# MurataMicroMB.net
KiCad netlist of a schematic drawn in EAGLE
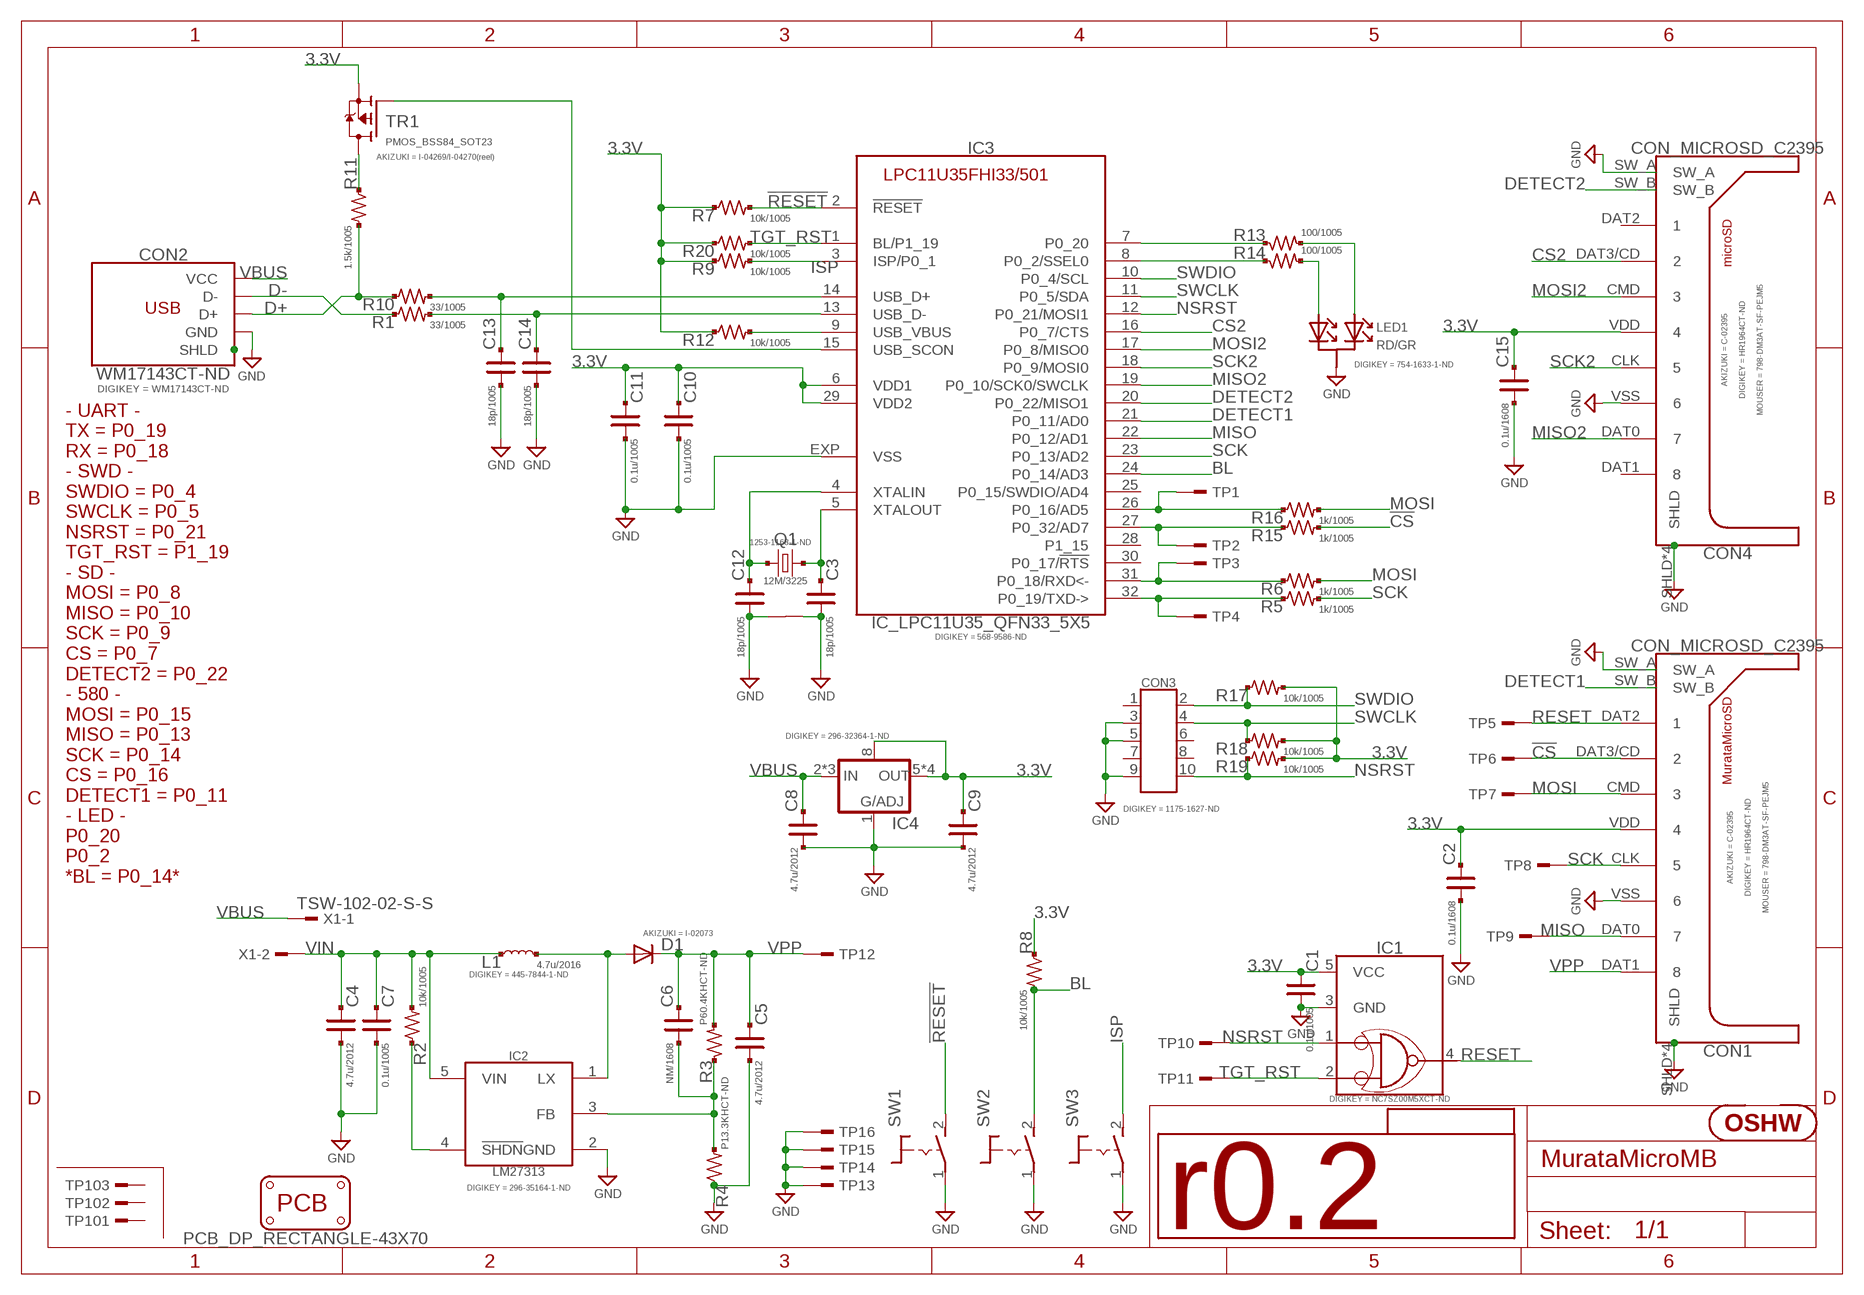
[diagram p0: schematic, sheet 1]

(export (version "E")
  (design (tool "Eeschema 10.0.6"))
  (components
    (comp (ref "C1")
      (value "0.1u/1005")
      (footprint "eagle-import:C0402")
      (libsource (lib "eagle-import") (part "C_SMD__10050.1U"))
    )
    (comp (ref "C2")
      (value "0.1u/1608")
      (footprint "eagle-import:CR_1608")
      (libsource (lib "eagle-import") (part "C_SMD__16080.1U"))
    )
    (comp (ref "C3")
      (value "18p/1005")
      (footprint "eagle-import:C0402")
      (libsource (lib "eagle-import") (part "C_SMD__100518P"))
    )
    (comp (ref "C4")
      (value "4.7u/2012")
      (footprint "eagle-import:CR_2125")
      (libsource (lib "eagle-import") (part "C_SMD__20124.7U"))
    )
    (comp (ref "C5")
      (value "4.7u/2012")
      (footprint "eagle-import:CR_2125")
      (libsource (lib "eagle-import") (part "C_SMD__20124.7U"))
    )
    (comp (ref "C6")
      (value "NM/1608")
      (footprint "eagle-import:CR_1608")
      (libsource (lib "eagle-import") (part "C_SMD__1608"))
    )
    (comp (ref "C7")
      (value "0.1u/1005")
      (footprint "eagle-import:C0402")
      (libsource (lib "eagle-import") (part "C_SMD__10050.1U"))
    )
    (comp (ref "C8")
      (value "4.7u/2012")
      (footprint "eagle-import:CR_2125")
      (libsource (lib "eagle-import") (part "C_SMD__20124.7U"))
    )
    (comp (ref "C9")
      (value "4.7u/2012")
      (footprint "eagle-import:CR_2125")
      (libsource (lib "eagle-import") (part "C_SMD__20124.7U"))
    )
    (comp (ref "C10")
      (value "0.1u/1005")
      (footprint "eagle-import:C0402")
      (libsource (lib "eagle-import") (part "C_SMD__10050.1U"))
    )
    (comp (ref "C11")
      (value "0.1u/1005")
      (footprint "eagle-import:C0402")
      (libsource (lib "eagle-import") (part "C_SMD__10050.1U"))
    )
    (comp (ref "C12")
      (value "18p/1005")
      (footprint "eagle-import:C0402")
      (libsource (lib "eagle-import") (part "C_SMD__100518P"))
    )
    (comp (ref "C13")
      (value "18p/1005")
      (footprint "eagle-import:C0402")
      (libsource (lib "eagle-import") (part "C_SMD__100518P"))
    )
    (comp (ref "C14")
      (value "18p/1005")
      (footprint "eagle-import:C0402")
      (libsource (lib "eagle-import") (part "C_SMD__100518P"))
    )
    (comp (ref "C15")
      (value "0.1u/1608")
      (footprint "eagle-import:CR_1608")
      (libsource (lib "eagle-import") (part "C_SMD__16080.1U"))
    )
    (comp (ref "CON1")
      (value "CON_MICROSD_C2395")
      (footprint "eagle-import:CON_MICROSD_C2395")
      (fields
        (field (name "AKIZUKI") "C-02395")
        (field (name "DIGIKEY") "HR1964CT-ND")
        (field (name "MOUSER") "798-DM3AT-SF-PEJM5")
      )
      (libsource (lib "eagle-import") (part "CON_MICROSD_C2395"))
    )
    (comp (ref "CON2")
      (value "WM17143CT-ND")
      (footprint "eagle-import:CON_USB_47589-0001MOLEX")
      (fields (field (name "DIGIKEY") "WM17143CT-ND"))
      (libsource (lib "eagle-import") (part "CON_USB_UB"))
    )
    (comp (ref "CON3")
      (value "CON_MIL_10_ARM")
      (footprint "eagle-import:CON_CORESIGHT10_1175-1627-ND")
      (fields (field (name "DIGIKEY") "1175-1627-ND"))
      (libsource (lib "eagle-import") (part "CON_MIL_10_ARM"))
    )
    (comp (ref "CON4")
      (value "CON_MICROSD_C2395")
      (footprint "eagle-import:CON_MICROSD_C2395")
      (fields
        (field (name "AKIZUKI") "C-02395")
        (field (name "DIGIKEY") "HR1964CT-ND")
        (field (name "MOUSER") "798-DM3AT-SF-PEJM5")
      )
      (libsource (lib "eagle-import") (part "CON_MICROSD_C2395"))
    )
    (comp (ref "D1")
      (value "40V2A")
      (footprint "eagle-import:DIODE_2125")
      (fields (field (name "AKIZUKI") "I-02073"))
      (libsource (lib "eagle-import") (part "DIODE2__SOD12340V2A"))
    )
    (comp (ref "GIT1")
      (value "GIT-REVISION")
      (footprint "eagle-import:GIT-REVISION")
      (libsource (lib "eagle-import") (part "GIT-REVISION"))
    )
    (comp (ref "IC1")
      (value "IC_TTL_SINGLE_74_00_SOT23")
      (footprint "eagle-import:SOT95P280X145-5N")
      (fields (field (name "DIGIKEY") "NC7SZ00M5XCT-ND"))
      (libsource (lib "eagle-import") (part "IC_TTL_SINGLE_74_00_SOT23"))
    )
    (comp (ref "IC2")
      (value "LM27313")
      (footprint "eagle-import:SOT95P280X145-5N")
      (fields (field (name "DIGIKEY") "296-35164-1-ND"))
      (libsource (lib "eagle-import") (part "IC_DCDC_LM27313_SOT23"))
    )
    (comp (ref "IC3")
      (value "IC_LPC11U35_QFN33_5X5")
      (footprint "eagle-import:HVQFN33")
      (fields (field (name "DIGIKEY") "568-9586-ND"))
      (libsource (lib "eagle-import") (part "IC_LPC11U_QFN33_5X535"))
    )
    (comp (ref "IC4")
      (value "LDO4_3.3_DRJ")
      (footprint "eagle-import:DFN80P410X410_8N")
      (fields (field (name "DIGIKEY") "296-32364-1-ND"))
      (libsource (lib "eagle-import") (part "LDO4__DRJ3.3"))
    )
    (comp (ref "ICON1")
      (value "r0.2")
      (footprint "eagle-import:ICON_REVISION2.0")
      (libsource (lib "eagle-import") (part "ICON_REVISION_2.0"))
    )
    (comp (ref "L1")
      (value "4.7u/2016")
      (footprint "eagle-import:L_2016")
      (fields (field (name "DIGIKEY") "445-7844-1-ND"))
      (libsource (lib "eagle-import") (part "INDUCTOR__20164.7U"))
    )
    (comp (ref "LED1")
      (value "RD/GR")
      (footprint "eagle-import:SOT105P300X130-3N")
      (fields (field (name "DIGIKEY") "754-1633-1-ND "))
      (libsource (lib "eagle-import") (part "LED2_A2K1_GR/RD"))
    )
    (comp (ref "PCB1")
      (value "PCB_DP_RECTANGLE-43X70")
      (footprint "eagle-import:DP7043_V1")
      (libsource (lib "eagle-import") (part "PCB_DP_RECTANGLE-43X70"))
    )
    (comp (ref "Q1")
      (value "12M/3225")
      (footprint "eagle-import:CLOCK_3225")
      (fields (field (name "DIGIKEY") "1253-1168-1-ND"))
      (libsource (lib "eagle-import") (part "CRYSTAL4__322512M"))
    )
    (comp (ref "R1")
      (value "33/1005")
      (footprint "eagle-import:C0402")
      (libsource (lib "eagle-import") (part "R_US__100533R"))
    )
    (comp (ref "R2")
      (value "10k/1005")
      (footprint "eagle-import:C0402")
      (libsource (lib "eagle-import") (part "R_US__100510K"))
    )
    (comp (ref "R3")
      (value "P60.4KHCT-ND")
      (footprint "eagle-import:R_1608_PADPAD")
      (libsource (lib "eagle-import") (part "R_US__160860.4K"))
    )
    (comp (ref "R4")
      (value "P13.3KHCT-ND")
      (footprint "eagle-import:R_1608_PADPAD")
      (libsource (lib "eagle-import") (part "R_US__160813.3K"))
    )
    (comp (ref "R5")
      (value "1k/1005")
      (footprint "eagle-import:C0402")
      (libsource (lib "eagle-import") (part "R_US__10051.0K"))
    )
    (comp (ref "R6")
      (value "1k/1005")
      (footprint "eagle-import:C0402")
      (libsource (lib "eagle-import") (part "R_US__10051.0K"))
    )
    (comp (ref "R7")
      (value "10k/1005")
      (footprint "eagle-import:C0402")
      (libsource (lib "eagle-import") (part "R_US__100510K"))
    )
    (comp (ref "R8")
      (value "10k/1005")
      (footprint "eagle-import:C0402")
      (libsource (lib "eagle-import") (part "R_US__100510K"))
    )
    (comp (ref "R9")
      (value "10k/1005")
      (footprint "eagle-import:C0402")
      (libsource (lib "eagle-import") (part "R_US__100510K"))
    )
    (comp (ref "R10")
      (value "33/1005")
      (footprint "eagle-import:C0402")
      (libsource (lib "eagle-import") (part "R_US__100533R"))
    )
    (comp (ref "R11")
      (value "1.5k/1005")
      (footprint "eagle-import:C0402")
      (libsource (lib "eagle-import") (part "R_US__10051.5K"))
    )
    (comp (ref "R12")
      (value "10k/1005")
      (footprint "eagle-import:C0402")
      (libsource (lib "eagle-import") (part "R_US__100510K"))
    )
    (comp (ref "R13")
      (value "100/1005")
      (footprint "eagle-import:C0402")
      (libsource (lib "eagle-import") (part "R_US__1005100R"))
    )
    (comp (ref "R14")
      (value "100/1005")
      (footprint "eagle-import:C0402")
      (libsource (lib "eagle-import") (part "R_US__1005100R"))
    )
    (comp (ref "R15")
      (value "1k/1005")
      (footprint "eagle-import:C0402")
      (libsource (lib "eagle-import") (part "R_US__10051.0K"))
    )
    (comp (ref "R16")
      (value "1k/1005")
      (footprint "eagle-import:C0402")
      (libsource (lib "eagle-import") (part "R_US__10051.0K"))
    )
    (comp (ref "R17")
      (value "10k/1005")
      (footprint "eagle-import:C0402")
      (libsource (lib "eagle-import") (part "R_US__100510K"))
    )
    (comp (ref "R18")
      (value "10k/1005")
      (footprint "eagle-import:C0402")
      (libsource (lib "eagle-import") (part "R_US__100510K"))
    )
    (comp (ref "R19")
      (value "10k/1005")
      (footprint "eagle-import:C0402")
      (libsource (lib "eagle-import") (part "R_US__100510K"))
    )
    (comp (ref "R20")
      (value "10k/1005")
      (footprint "eagle-import:C0402")
      (libsource (lib "eagle-import") (part "R_US__100510K"))
    )
    (comp (ref "SW1")
      (value "TACTSW2_FSM2JMTR")
      (footprint "eagle-import:SW_TACTSW_FSM2JMTR")
      (libsource (lib "eagle-import") (part "TACTSW2_FSM2JMTR"))
    )
    (comp (ref "SW2")
      (value "TACTSW2_FSM2JMTR")
      (footprint "eagle-import:SW_TACTSW_FSM2JMTR")
      (libsource (lib "eagle-import") (part "TACTSW2_FSM2JMTR"))
    )
    (comp (ref "SW3")
      (value "TACTSW2_FSM2JMTR")
      (footprint "eagle-import:SW_TACTSW_FSM2JMTR")
      (libsource (lib "eagle-import") (part "TACTSW2_FSM2JMTR"))
    )
    (comp (ref "TP1")
      (value "TESTPAD_1608")
      (footprint "eagle-import:TP_1608")
      (libsource (lib "eagle-import") (part "TESTPAD_1608"))
    )
    (comp (ref "TP2")
      (value "TESTPAD_1608")
      (footprint "eagle-import:TP_1608")
      (libsource (lib "eagle-import") (part "TESTPAD_1608"))
    )
    (comp (ref "TP3")
      (value "TESTPAD_1608")
      (footprint "eagle-import:TP_1608")
      (libsource (lib "eagle-import") (part "TESTPAD_1608"))
    )
    (comp (ref "TP4")
      (value "TESTPAD_1608")
      (footprint "eagle-import:TP_1608")
      (libsource (lib "eagle-import") (part "TESTPAD_1608"))
    )
    (comp (ref "TP5")
      (value "TESTPAD")
      (footprint "eagle-import:TP06RECT")
      (libsource (lib "eagle-import") (part "TESTPAD"))
    )
    (comp (ref "TP6")
      (value "TESTPAD")
      (footprint "eagle-import:TP06RECT")
      (libsource (lib "eagle-import") (part "TESTPAD"))
    )
    (comp (ref "TP7")
      (value "TESTPAD")
      (footprint "eagle-import:TP06RECT")
      (libsource (lib "eagle-import") (part "TESTPAD"))
    )
    (comp (ref "TP8")
      (value "TESTPAD")
      (footprint "eagle-import:TP06RECT")
      (libsource (lib "eagle-import") (part "TESTPAD"))
    )
    (comp (ref "TP9")
      (value "TESTPAD")
      (footprint "eagle-import:TP06RECT")
      (libsource (lib "eagle-import") (part "TESTPAD"))
    )
    (comp (ref "TP10")
      (value "TESTPAD")
      (footprint "eagle-import:TP06RECT")
      (libsource (lib "eagle-import") (part "TESTPAD"))
    )
    (comp (ref "TP11")
      (value "TESTPAD")
      (footprint "eagle-import:TP06RECT")
      (libsource (lib "eagle-import") (part "TESTPAD"))
    )
    (comp (ref "TP12")
      (value "TESTPAD")
      (footprint "eagle-import:TP06RECT")
      (libsource (lib "eagle-import") (part "TESTPAD"))
    )
    (comp (ref "TP13")
      (value "TESTPAD_4020")
      (footprint "eagle-import:TP_4020")
      (libsource (lib "eagle-import") (part "TESTPAD_4020"))
    )
    (comp (ref "TP14")
      (value "TESTPAD_4020")
      (footprint "eagle-import:TP_4020")
      (libsource (lib "eagle-import") (part "TESTPAD_4020"))
    )
    (comp (ref "TP15")
      (value "TESTPAD_4020")
      (footprint "eagle-import:TP_4020")
      (libsource (lib "eagle-import") (part "TESTPAD_4020"))
    )
    (comp (ref "TP16")
      (value "TESTPAD_4020")
      (footprint "eagle-import:TP_4020")
      (libsource (lib "eagle-import") (part "TESTPAD_4020"))
    )
    (comp (ref "TP101")
      (value "TESTPAD_F")
      (footprint "eagle-import:FIDUCIAL")
      (libsource (lib "eagle-import") (part "TESTPAD_F"))
    )
    (comp (ref "TP102")
      (value "TESTPAD_F")
      (footprint "eagle-import:FIDUCIAL")
      (libsource (lib "eagle-import") (part "TESTPAD_F"))
    )
    (comp (ref "TP103")
      (value "TESTPAD_F")
      (footprint "eagle-import:FIDUCIAL")
      (libsource (lib "eagle-import") (part "TESTPAD_F"))
    )
    (comp (ref "TR1")
      (value "PMOS_BSS84_SOT23")
      (footprint "eagle-import:SOT95P300X140-3N")
      (fields (field (name "AKIZUKI") "I-04269/I-04270(reel)"))
      (libsource (lib "eagle-import") (part "PMOS__SOT23BSS84"))
    )
    (comp (ref "U$1")
      (value "ICON_OSHW")
      (footprint "eagle-import:ICON_OSHW")
      (libsource (lib "eagle-import") (part "ICON_OSHW"))
    )
    (comp (ref "X1")
      (value "TSW-102-02-S-S")
      (footprint "eagle-import:TSW-102-02-S-S")
      (libsource (lib "eagle-import") (part "TSW-102-02-S-S"))
    )
  )
  (nets
    (net (code "1") (name "/3.3V") (class "Default")
      (node (ref "C1") (pin "1") (pinfunction "1_1") (pintype "passive"))
      (node (ref "C10") (pin "1") (pinfunction "1_1") (pintype "passive"))
      (node (ref "C11") (pin "1") (pinfunction "1_1") (pintype "passive"))
      (node (ref "C15") (pin "1") (pinfunction "1_1") (pintype "passive"))
      (node (ref "C2") (pin "1") (pinfunction "1_1") (pintype "passive"))
      (node (ref "C9") (pin "1") (pinfunction "1_1") (pintype "passive"))
      (node (ref "CON1") (pin "VDD") (pinfunction "4_VDD") (pintype "power_in"))
      (node (ref "CON4") (pin "VDD") (pinfunction "4_VDD") (pintype "power_in"))
      (node (ref "IC1") (pin "5") (pinfunction "VCC_5") (pintype "power_in"))
      (node (ref "IC3") (pin "29") (pinfunction "VDD2_29") (pintype "bidirectional"))
      (node (ref "IC3") (pin "6") (pinfunction "VDD1_6") (pintype "bidirectional"))
      (node (ref "IC4") (pin "5") (pinfunction "OUT_5") (pintype "power_in"))
      (node (ref "IC4") (pin "6") (pinfunction "OUT_6") (pintype "power_in"))
      (node (ref "IC4") (pin "7") (pinfunction "OUT_7") (pintype "power_in"))
      (node (ref "IC4") (pin "8") (pinfunction "OUT/EN/NC_8") (pintype "tri_state"))
      (node (ref "IC4") (pin "EP") (pinfunction "OUT_EP") (pintype "power_in"))
      (node (ref "R12") (pin "1") (pinfunction "1_1") (pintype "passive"))
      (node (ref "R17") (pin "2") (pinfunction "2_2") (pintype "passive"))
      (node (ref "R18") (pin "2") (pinfunction "2_2") (pintype "passive"))
      (node (ref "R19") (pin "2") (pinfunction "2_2") (pintype "passive"))
      (node (ref "R20") (pin "1") (pinfunction "1_1") (pintype "passive"))
      (node (ref "R7") (pin "1") (pinfunction "1_1") (pintype "passive"))
      (node (ref "R8") (pin "1") (pinfunction "1_1") (pintype "passive"))
      (node (ref "R9") (pin "1") (pinfunction "1_1") (pintype "passive"))
      (node (ref "TR1") (pin "2") (pinfunction "S_2") (pintype "passive"))
    )
    (net (code "2") (name "/BL") (class "Default")
      (node (ref "IC3") (pin "24") (pinfunction "P0_14/AD3_24") (pintype "bidirectional"))
      (node (ref "R8") (pin "2") (pinfunction "2_2") (pintype "passive"))
      (node (ref "SW2") (pin "2") (pinfunction "S_2") (pintype "passive"))
    )
    (net (code "3") (name "/CS2") (class "Default")
      (node (ref "CON4") (pin "DAT3/CD") (pinfunction "2_DAT3/CD") (pintype "bidirectional"))
      (node (ref "IC3") (pin "16") (pinfunction "P0_7/CTS_16") (pintype "bidirectional"))
    )
    (net (code "4") (name "/D+") (class "Default")
      (node (ref "CON2") (pin "3") (pinfunction "D+_3") (pintype "bidirectional"))
      (node (ref "R10") (pin "1") (pinfunction "1_1") (pintype "passive"))
      (node (ref "R11") (pin "2") (pinfunction "2_2") (pintype "passive"))
    )
    (net (code "5") (name "/D-") (class "Default")
      (node (ref "CON2") (pin "2") (pinfunction "D-_2") (pintype "bidirectional"))
      (node (ref "R1") (pin "1") (pinfunction "1_1") (pintype "passive"))
    )
    (net (code "6") (name "/DETECT1") (class "Default")
      (node (ref "CON1") (pin "SW_B") (pinfunction "SW_B_SW_B") (pintype "bidirectional"))
      (node (ref "IC3") (pin "21") (pinfunction "P0_11/AD0_21") (pintype "bidirectional"))
    )
    (net (code "7") (name "/DETECT2") (class "Default")
      (node (ref "CON4") (pin "SW_B") (pinfunction "SW_B_SW_B") (pintype "bidirectional"))
      (node (ref "IC3") (pin "20") (pinfunction "P0_22/MISO1_20") (pintype "bidirectional"))
    )
    (net (code "8") (name "/ISP") (class "Default")
      (node (ref "IC3") (pin "3") (pinfunction "ISP/P0_1_3") (pintype "bidirectional"))
      (node (ref "R9") (pin "2") (pinfunction "2_2") (pintype "passive"))
      (node (ref "SW3") (pin "2") (pinfunction "S_2") (pintype "passive"))
    )
    (net (code "9") (name "/MISO") (class "Default")
      (node (ref "CON1") (pin "DAT0") (pinfunction "7_DAT0") (pintype "bidirectional"))
      (node (ref "IC3") (pin "22") (pinfunction "P0_12/AD1_22") (pintype "bidirectional"))
      (node (ref "TP9") (pin "TP") (pinfunction "1_TP") (pintype "passive"))
    )
    (net (code "10") (name "/MISO2") (class "Default")
      (node (ref "CON4") (pin "DAT0") (pinfunction "7_DAT0") (pintype "bidirectional"))
      (node (ref "IC3") (pin "19") (pinfunction "P0_10/SCK0/SWCLK_19") (pintype "bidirectional"))
    )
    (net (code "11") (name "/MOSI") (class "Default")
      (node (ref "CON1") (pin "CMD") (pinfunction "3_CMD") (pintype "bidirectional"))
      (node (ref "R16") (pin "2") (pinfunction "2_2") (pintype "passive"))
      (node (ref "R6") (pin "2") (pinfunction "2_2") (pintype "passive"))
      (node (ref "TP7") (pin "TP") (pinfunction "1_TP") (pintype "passive"))
    )
    (net (code "12") (name "/MOSI2") (class "Default")
      (node (ref "CON4") (pin "CMD") (pinfunction "3_CMD") (pintype "bidirectional"))
      (node (ref "IC3") (pin "17") (pinfunction "P0_8/MISO0_17") (pintype "bidirectional"))
    )
    (net (code "13") (name "/NSRST") (class "Default")
      (node (ref "CON3") (pin "10") (pinfunction "10_10") (pintype "bidirectional"))
      (node (ref "IC1") (pin "1") (pinfunction "1A_1") (pintype "input"))
      (node (ref "IC3") (pin "12") (pinfunction "P0_21/MOSI1_12") (pintype "bidirectional"))
      (node (ref "R19") (pin "1") (pinfunction "1_1") (pintype "passive"))
      (node (ref "TP10") (pin "TP") (pinfunction "1_TP") (pintype "passive"))
    )
    (net (code "14") (name "/RESET") (class "Default")
      (node (ref "CON1") (pin "DAT2") (pinfunction "1_DAT2") (pintype "bidirectional"))
      (node (ref "IC1") (pin "4") (pinfunction "1Y_4") (pintype "output"))
      (node (ref "TP5") (pin "TP") (pinfunction "1_TP") (pintype "passive"))
    )
    (net (code "15") (name "/SCK") (class "Default")
      (node (ref "CON1") (pin "CLK") (pinfunction "5_CLK") (pintype "bidirectional"))
      (node (ref "IC3") (pin "23") (pinfunction "P0_13/AD2_23") (pintype "bidirectional"))
      (node (ref "R5") (pin "2") (pinfunction "2_2") (pintype "passive"))
      (node (ref "TP8") (pin "TP") (pinfunction "1_TP") (pintype "passive"))
    )
    (net (code "16") (name "/SCK2") (class "Default")
      (node (ref "CON4") (pin "CLK") (pinfunction "5_CLK") (pintype "bidirectional"))
      (node (ref "IC3") (pin "18") (pinfunction "P0_9/MOSI0_18") (pintype "bidirectional"))
    )
    (net (code "17") (name "/SWCLK") (class "Default")
      (node (ref "CON3") (pin "4") (pinfunction "4_4") (pintype "bidirectional"))
      (node (ref "IC3") (pin "11") (pinfunction "P0_5/SDA_11") (pintype "bidirectional"))
      (node (ref "R18") (pin "1") (pinfunction "1_1") (pintype "passive"))
    )
    (net (code "18") (name "/SWDIO") (class "Default")
      (node (ref "CON3") (pin "2") (pinfunction "2_2") (pintype "bidirectional"))
      (node (ref "IC3") (pin "10") (pinfunction "P0_4/SCL_10") (pintype "bidirectional"))
      (node (ref "R17") (pin "1") (pinfunction "1_1") (pintype "passive"))
    )
    (net (code "19") (name "/TGT_RST") (class "Default")
      (node (ref "IC1") (pin "2") (pinfunction "1B_2") (pintype "input"))
      (node (ref "IC3") (pin "1") (pinfunction "BL/P1_19_1") (pintype "bidirectional"))
      (node (ref "R20") (pin "2") (pinfunction "2_2") (pintype "passive"))
      (node (ref "TP11") (pin "TP") (pinfunction "1_TP") (pintype "passive"))
    )
    (net (code "20") (name "/VBUS") (class "Default")
      (node (ref "C8") (pin "1") (pinfunction "1_1") (pintype "passive"))
      (node (ref "CON2") (pin "1") (pinfunction "VCC_1") (pintype "power_in"))
      (node (ref "IC4") (pin "2") (pinfunction "IN_2") (pintype "power_in"))
      (node (ref "IC4") (pin "3") (pinfunction "IN_3") (pintype "power_in"))
      (node (ref "IC4") (pin "4") (pinfunction "IN_4") (pintype "power_in"))
      (node (ref "X1") (pin "1") (pinfunction "1_1") (pintype "passive"))
    )
    (net (code "21") (name "/VIN") (class "Default")
      (node (ref "C4") (pin "1") (pinfunction "1_1") (pintype "passive"))
      (node (ref "C7") (pin "1") (pinfunction "1_1") (pintype "passive"))
      (node (ref "IC2") (pin "5") (pinfunction "VIN_5") (pintype "bidirectional"))
      (node (ref "L1") (pin "1") (pinfunction "1_1") (pintype "passive"))
      (node (ref "R2") (pin "2") (pinfunction "2_2") (pintype "passive"))
      (node (ref "X1") (pin "2") (pinfunction "1_2") (pintype "passive"))
    )
    (net (code "22") (name "/VPP") (class "Default")
      (node (ref "C5") (pin "1") (pinfunction "1_1") (pintype "passive"))
      (node (ref "C6") (pin "1") (pinfunction "1_1") (pintype "passive"))
      (node (ref "CON1") (pin "DAT1") (pinfunction "8_DAT1") (pintype "bidirectional"))
      (node (ref "D1") (pin "K") (pinfunction "C_K") (pintype "passive"))
      (node (ref "R3") (pin "2") (pinfunction "2_2") (pintype "passive"))
      (node (ref "TP12") (pin "TP") (pinfunction "1_TP") (pintype "passive"))
    )
    (net (code "23") (name "/~{CS}") (class "Default")
      (node (ref "CON1") (pin "DAT3/CD") (pinfunction "2_DAT3/CD") (pintype "bidirectional"))
      (node (ref "R15") (pin "2") (pinfunction "2_2") (pintype "passive"))
      (node (ref "TP6") (pin "TP") (pinfunction "1_TP") (pintype "passive"))
    )
    (net (code "24") (name "/~{RESET}") (class "Default")
      (node (ref "IC3") (pin "2") (pinfunction "~{RESET}_2") (pintype "bidirectional"))
      (node (ref "R7") (pin "2") (pinfunction "2_2") (pintype "passive"))
      (node (ref "SW1") (pin "2") (pinfunction "S_2") (pintype "passive"))
    )
    (net (code "25") (name "GND") (class "Default")
      (node (ref "C1") (pin "2") (pinfunction "2_2") (pintype "passive"))
      (node (ref "C10") (pin "2") (pinfunction "2_2") (pintype "passive"))
      (node (ref "C11") (pin "2") (pinfunction "2_2") (pintype "passive"))
      (node (ref "C12") (pin "2") (pinfunction "2_2") (pintype "passive"))
      (node (ref "C13") (pin "2") (pinfunction "2_2") (pintype "passive"))
      (node (ref "C14") (pin "2") (pinfunction "2_2") (pintype "passive"))
      (node (ref "C15") (pin "2") (pinfunction "2_2") (pintype "passive"))
      (node (ref "C2") (pin "2") (pinfunction "2_2") (pintype "passive"))
      (node (ref "C3") (pin "2") (pinfunction "2_2") (pintype "passive"))
      (node (ref "C4") (pin "2") (pinfunction "2_2") (pintype "passive"))
      (node (ref "C5") (pin "2") (pinfunction "2_2") (pintype "passive"))
      (node (ref "C7") (pin "2") (pinfunction "2_2") (pintype "passive"))
      (node (ref "C8") (pin "2") (pinfunction "2_2") (pintype "passive"))
      (node (ref "C9") (pin "2") (pinfunction "2_2") (pintype "passive"))
      (node (ref "CON1") (pin "SHLD") (pinfunction "SHLD_SHLD") (pintype "bidirectional"))
      (node (ref "CON1") (pin "SHLD@2") (pinfunction "SHLD_SHLD@2") (pintype "bidirectional"))
      (node (ref "CON1") (pin "SHLD@3") (pinfunction "SHLD_SHLD@3") (pintype "bidirectional"))
      (node (ref "CON1") (pin "SHLD@4") (pinfunction "SHLD_SHLD@4") (pintype "bidirectional"))
      (node (ref "CON1") (pin "SW_A") (pinfunction "SW_A_SW_A") (pintype "bidirectional"))
      (node (ref "CON1") (pin "VSS") (pinfunction "6_VSS") (pintype "power_in"))
      (node (ref "CON2") (pin "5") (pinfunction "GND_5") (pintype "power_in"))
      (node (ref "CON3") (pin "3") (pinfunction "3_3") (pintype "bidirectional"))
      (node (ref "CON3") (pin "5") (pinfunction "5_5") (pintype "bidirectional"))
      (node (ref "CON3") (pin "9") (pinfunction "9_9") (pintype "bidirectional"))
      (node (ref "CON4") (pin "SHLD") (pinfunction "SHLD_SHLD") (pintype "bidirectional"))
      (node (ref "CON4") (pin "SHLD@2") (pinfunction "SHLD_SHLD@2") (pintype "bidirectional"))
      (node (ref "CON4") (pin "SHLD@3") (pinfunction "SHLD_SHLD@3") (pintype "bidirectional"))
      (node (ref "CON4") (pin "SHLD@4") (pinfunction "SHLD_SHLD@4") (pintype "bidirectional"))
      (node (ref "CON4") (pin "SW_A") (pinfunction "SW_A_SW_A") (pintype "bidirectional"))
      (node (ref "CON4") (pin "VSS") (pinfunction "6_VSS") (pintype "power_in"))
      (node (ref "IC1") (pin "3") (pinfunction "GND_3") (pintype "power_in"))
      (node (ref "IC2") (pin "2") (pinfunction "GND_2") (pintype "bidirectional"))
      (node (ref "IC3") (pin "EXP") (pinfunction "VSS_EXP") (pintype "bidirectional"))
      (node (ref "IC4") (pin "1") (pinfunction "ADJ_1") (pintype "power_in"))
      (node (ref "LED1") (pin "3") (pinfunction "K1_3") (pintype "bidirectional"))
      (node (ref "Q1") (pin "2") (pinfunction "P$1_2") (pintype "bidirectional"))
      (node (ref "Q1") (pin "4") (pinfunction "P$2_4") (pintype "bidirectional"))
      (node (ref "R4") (pin "1") (pinfunction "1_1") (pintype "passive"))
      (node (ref "SW1") (pin "1") (pinfunction "P_1") (pintype "passive"))
      (node (ref "SW2") (pin "1") (pinfunction "P_1") (pintype "passive"))
      (node (ref "SW3") (pin "1") (pinfunction "P_1") (pintype "passive"))
      (node (ref "TP13") (pin "TP") (pinfunction "1_TP") (pintype "passive"))
      (node (ref "TP14") (pin "TP") (pinfunction "1_TP") (pintype "passive"))
      (node (ref "TP15") (pin "TP") (pinfunction "1_TP") (pintype "passive"))
      (node (ref "TP16") (pin "TP") (pinfunction "1_TP") (pintype "passive"))
    )
    (net (code "26") (name "Net-(CON2-SHLD-PadSHD$1)") (class "Default")
      (node (ref "CON2") (pin "SHD") (pinfunction "SHLD_SHD") (pintype "bidirectional"))
      (node (ref "CON2") (pin "SHD$1") (pinfunction "SHLD_SHD$1") (pintype "bidirectional"))
      (node (ref "CON2") (pin "SHD$2") (pinfunction "SHLD_SHD$2") (pintype "bidirectional"))
      (node (ref "CON2") (pin "SHD$3") (pinfunction "SHLD_SHD$3") (pintype "bidirectional"))
      (node (ref "CON2") (pin "SHD$4") (pinfunction "SHLD_SHD$4") (pintype "bidirectional"))
      (node (ref "CON2") (pin "SHD$5") (pinfunction "SHLD_SHD$5") (pintype "bidirectional"))
      (node (ref "CON2") (pin "SHD$6") (pinfunction "SHLD_SHD$6") (pintype "bidirectional"))
      (node (ref "CON2") (pin "SHD$7") (pinfunction "SHLD_SHD$7") (pintype "bidirectional"))
    )
    (net (code "27") (name "Net-(IC2-FB)") (class "Default")
      (node (ref "C6") (pin "2") (pinfunction "2_2") (pintype "passive"))
      (node (ref "IC2") (pin "3") (pinfunction "FB_3") (pintype "bidirectional"))
      (node (ref "R3") (pin "1") (pinfunction "1_1") (pintype "passive"))
      (node (ref "R4") (pin "2") (pinfunction "2_2") (pintype "passive"))
    )
    (net (code "28") (name "Net-(IC2-LX)") (class "Default")
      (node (ref "D1") (pin "A") (pinfunction "A_A") (pintype "passive"))
      (node (ref "IC2") (pin "1") (pinfunction "LX_1") (pintype "bidirectional"))
      (node (ref "L1") (pin "2") (pinfunction "2_2") (pintype "passive"))
    )
    (net (code "29") (name "Net-(IC2-~{SHDN})") (class "Default")
      (node (ref "IC2") (pin "4") (pinfunction "~{SHDN}_4") (pintype "bidirectional"))
      (node (ref "R2") (pin "1") (pinfunction "1_1") (pintype "passive"))
    )
    (net (code "30") (name "Net-(IC3-P0_2{slash}SSEL0)") (class "Default")
      (node (ref "IC3") (pin "8") (pinfunction "P0_2/SSEL0_8") (pintype "bidirectional"))
      (node (ref "R14") (pin "1") (pinfunction "1_1") (pintype "passive"))
    )
    (net (code "31") (name "Net-(IC3-P0_16{slash}AD5)") (class "Default")
      (node (ref "IC3") (pin "26") (pinfunction "P0_16/AD5_26") (pintype "bidirectional"))
      (node (ref "R16") (pin "1") (pinfunction "1_1") (pintype "passive"))
      (node (ref "TP1") (pin "TP") (pinfunction "1_TP") (pintype "passive"))
    )
    (net (code "32") (name "Net-(IC3-P0_18{slash}RXD<-)") (class "Default")
      (node (ref "IC3") (pin "31") (pinfunction "P0_18/RXD<-_31") (pintype "bidirectional"))
      (node (ref "R6") (pin "1") (pinfunction "1_1") (pintype "passive"))
      (node (ref "TP3") (pin "TP") (pinfunction "1_TP") (pintype "passive"))
    )
    (net (code "33") (name "Net-(IC3-P0_19{slash}TXD->)") (class "Default")
      (node (ref "IC3") (pin "32") (pinfunction "P0_19/TXD->_32") (pintype "bidirectional"))
      (node (ref "R5") (pin "1") (pinfunction "1_1") (pintype "passive"))
      (node (ref "TP4") (pin "TP") (pinfunction "1_TP") (pintype "passive"))
    )
    (net (code "34") (name "Net-(IC3-P0_20)") (class "Default")
      (node (ref "IC3") (pin "7") (pinfunction "P0_20_7") (pintype "bidirectional"))
      (node (ref "R13") (pin "1") (pinfunction "1_1") (pintype "passive"))
    )
    (net (code "35") (name "Net-(IC3-P0_32{slash}AD7)") (class "Default")
      (node (ref "IC3") (pin "27") (pinfunction "P0_32/AD7_27") (pintype "bidirectional"))
      (node (ref "R15") (pin "1") (pinfunction "1_1") (pintype "passive"))
      (node (ref "TP2") (pin "TP") (pinfunction "1_TP") (pintype "passive"))
    )
    (net (code "36") (name "Net-(IC3-USB_D+)") (class "Default")
      (node (ref "C13") (pin "1") (pinfunction "1_1") (pintype "passive"))
      (node (ref "IC3") (pin "14") (pinfunction "USB_D+_14") (pintype "bidirectional"))
      (node (ref "R10") (pin "2") (pinfunction "2_2") (pintype "passive"))
    )
    (net (code "37") (name "Net-(IC3-USB_D-)") (class "Default")
      (node (ref "C14") (pin "1") (pinfunction "1_1") (pintype "passive"))
      (node (ref "IC3") (pin "13") (pinfunction "USB_D-_13") (pintype "bidirectional"))
      (node (ref "R1") (pin "2") (pinfunction "2_2") (pintype "passive"))
    )
    (net (code "38") (name "Net-(IC3-USB_SCON)") (class "Default")
      (node (ref "IC3") (pin "15") (pinfunction "USB_SCON_15") (pintype "bidirectional"))
      (node (ref "TR1") (pin "1") (pinfunction "G_1") (pintype "passive"))
    )
    (net (code "39") (name "Net-(IC3-USB_VBUS)") (class "Default")
      (node (ref "IC3") (pin "9") (pinfunction "USB_VBUS_9") (pintype "bidirectional"))
      (node (ref "R12") (pin "2") (pinfunction "2_2") (pintype "passive"))
    )
    (net (code "40") (name "Net-(IC3-XTALIN)") (class "Default")
      (node (ref "C12") (pin "1") (pinfunction "1_1") (pintype "passive"))
      (node (ref "IC3") (pin "4") (pinfunction "XTALIN_4") (pintype "bidirectional"))
      (node (ref "Q1") (pin "1") (pinfunction "1_1") (pintype "passive"))
    )
    (net (code "41") (name "Net-(IC3-XTALOUT)") (class "Default")
      (node (ref "C3") (pin "1") (pinfunction "1_1") (pintype "passive"))
      (node (ref "IC3") (pin "5") (pinfunction "XTALOUT_5") (pintype "bidirectional"))
      (node (ref "Q1") (pin "3") (pinfunction "2_3") (pintype "passive"))
    )
    (net (code "42") (name "Net-(LED1-A1)") (class "Default")
      (node (ref "LED1") (pin "1") (pinfunction "A1_1") (pintype "bidirectional"))
      (node (ref "R14") (pin "2") (pinfunction "2_2") (pintype "passive"))
    )
    (net (code "43") (name "Net-(LED1-A2)") (class "Default")
      (node (ref "LED1") (pin "2") (pinfunction "A2_2") (pintype "bidirectional"))
      (node (ref "R13") (pin "2") (pinfunction "2_2") (pintype "passive"))
    )
    (net (code "44") (name "Net-(TR1-D)") (class "Default")
      (node (ref "R11") (pin "1") (pinfunction "1_1") (pintype "passive"))
      (node (ref "TR1") (pin "3") (pinfunction "D_3") (pintype "passive"))
    )
    (net (code "45") (name "unconnected-(CON3-Pad1)") (class "Default")
      (node (ref "CON3") (pin "1") (pinfunction "1_1") (pintype "bidirectional"))
    )
    (net (code "46") (name "unconnected-(CON3-Pad6)") (class "Default")
      (node (ref "CON3") (pin "6") (pinfunction "6_6") (pintype "bidirectional"))
    )
    (net (code "47") (name "unconnected-(CON3-Pad7)") (class "Default")
      (node (ref "CON3") (pin "7") (pinfunction "7_7") (pintype "bidirectional"))
    )
    (net (code "48") (name "unconnected-(CON3-Pad8)") (class "Default")
      (node (ref "CON3") (pin "8") (pinfunction "8_8") (pintype "bidirectional"))
    )
    (net (code "49") (name "unconnected-(CON4-1-PadDAT2)") (class "Default")
      (node (ref "CON4") (pin "DAT2") (pinfunction "1_DAT2") (pintype "bidirectional"))
    )
    (net (code "50") (name "unconnected-(CON4-8-PadDAT1)") (class "Default")
      (node (ref "CON4") (pin "DAT1") (pinfunction "8_DAT1") (pintype "bidirectional"))
    )
    (net (code "51") (name "unconnected-(IC3-P0_15{slash}SWDIO{slash}AD4-Pad25)") (class "Default")
      (node (ref "IC3") (pin "25") (pinfunction "P0_15/SWDIO/AD4_25") (pintype "bidirectional"))
    )
    (net (code "52") (name "unconnected-(IC3-P0_17{slash}~{RTS}-Pad30)") (class "Default")
      (node (ref "IC3") (pin "30") (pinfunction "P0_17/~{RTS}_30") (pintype "bidirectional"))
    )
    (net (code "53") (name "unconnected-(IC3-P1_15-Pad28)") (class "Default")
      (node (ref "IC3") (pin "28") (pinfunction "P1_15_28") (pintype "bidirectional"))
    )
    (net (code "54") (name "unconnected-(TP101-1-PadTP)") (class "Default")
      (node (ref "TP101") (pin "TP") (pinfunction "1_TP") (pintype "passive"))
    )
    (net (code "55") (name "unconnected-(TP102-1-PadTP)") (class "Default")
      (node (ref "TP102") (pin "TP") (pinfunction "1_TP") (pintype "passive"))
    )
    (net (code "56") (name "unconnected-(TP103-1-PadTP)") (class "Default")
      (node (ref "TP103") (pin "TP") (pinfunction "1_TP") (pintype "passive"))
    )
  )
)
